# pth.net
KiCad netlist of a schematic drawn in EAGLE
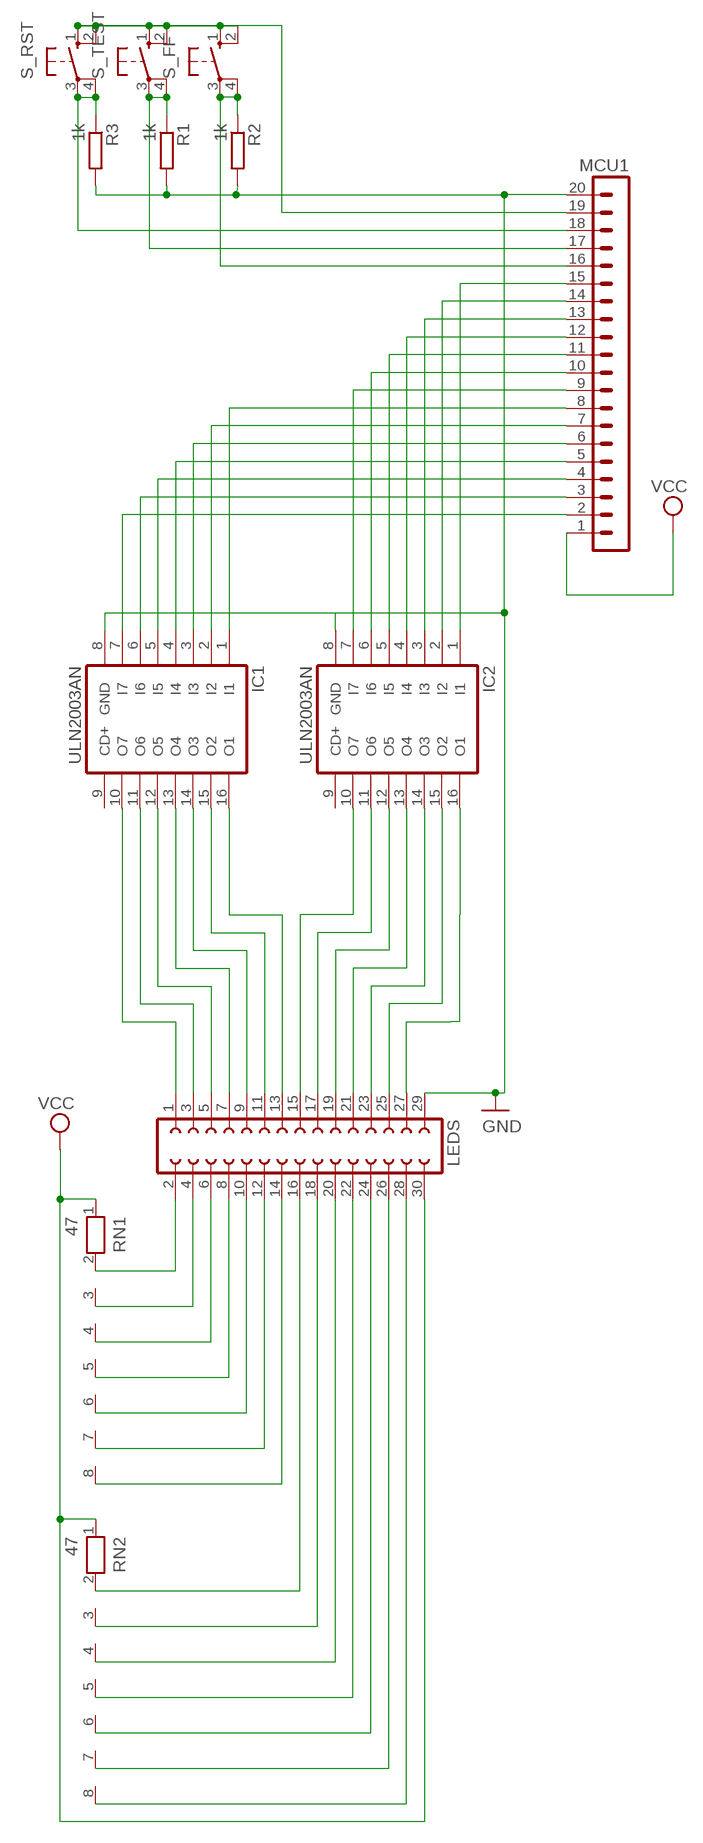
[diagram p0: schematic, sheet 1]

(export (version "E")
  (design (tool "Eeschema 10.0.6"))
  (components
    (comp (ref "IC1")
      (value "ULN2003AN")
      (footprint "eagle-import:DIL16")
      (libsource (lib "eagle-import") (part "ULN2003AN"))
    )
    (comp (ref "IC2")
      (value "ULN2003AN")
      (footprint "eagle-import:DIL16")
      (libsource (lib "eagle-import") (part "ULN2003AN"))
    )
    (comp (ref "LEDS")
      (value "FE15-2")
      (footprint "eagle-import:FE15-2")
      (libsource (lib "eagle-import") (part "FE15-2"))
    )
    (comp (ref "MCU1")
      (value "MA20-1")
      (footprint "eagle-import:MA20-1")
      (libsource (lib "eagle-import") (part "MA20-1"))
    )
    (comp (ref "R1")
      (value "1k")
      (footprint "eagle-import:0207_10")
      (libsource (lib "eagle-import") (part "R-EU_0207/10"))
    )
    (comp (ref "R2")
      (value "1k")
      (footprint "eagle-import:0207_10")
      (libsource (lib "eagle-import") (part "R-EU_0207/10"))
    )
    (comp (ref "R3")
      (value "1k")
      (footprint "eagle-import:0207_10")
      (libsource (lib "eagle-import") (part "R-EU_0207/10"))
    )
    (comp (ref "RN1")
      (value "47")
      (footprint "eagle-import:RN-8")
      (libsource (lib "eagle-import") (part "RN07"))
    )
    (comp (ref "RN2")
      (value "47")
      (footprint "eagle-import:RN-8")
      (libsource (lib "eagle-import") (part "RN07"))
    )
    (comp (ref "S_FF")
      (value "10-XX")
      (footprint "eagle-import:B3F-10XX")
      (fields (field (name "MPN") "B3F-1000"))
      (libsource (lib "eagle-import") (part "10-XX"))
    )
    (comp (ref "S_RST")
      (value "10-XX")
      (footprint "eagle-import:B3F-10XX")
      (fields (field (name "MPN") "B3F-1000"))
      (libsource (lib "eagle-import") (part "10-XX"))
    )
    (comp (ref "S_TEST")
      (value "10-XX")
      (footprint "eagle-import:B3F-10XX")
      (fields (field (name "MPN") "B3F-1000"))
      (libsource (lib "eagle-import") (part "10-XX"))
    )
  )
  (nets
    (net (code "1") (name "GND") (class "Default")
      (node (ref "IC1") (pin "8") (pinfunction "GND_8") (pintype "power_in"))
      (node (ref "IC2") (pin "8") (pinfunction "GND_8") (pintype "power_in"))
      (node (ref "LEDS") (pin "29") (pinfunction "29_29") (pintype "passive"))
      (node (ref "MCU1") (pin "20") (pinfunction "20_20") (pintype "passive"))
      (node (ref "R1") (pin "2") (pinfunction "2_2") (pintype "passive"))
      (node (ref "R2") (pin "2") (pinfunction "2_2") (pintype "passive"))
      (node (ref "R3") (pin "2") (pinfunction "2_2") (pintype "passive"))
    )
    (net (code "2") (name "Net-(IC1-I1)") (class "Default")
      (node (ref "IC1") (pin "1") (pinfunction "I1_1") (pintype "input"))
      (node (ref "MCU1") (pin "8") (pinfunction "8_8") (pintype "passive"))
    )
    (net (code "3") (name "Net-(IC1-I2)") (class "Default")
      (node (ref "IC1") (pin "2") (pinfunction "I2_2") (pintype "input"))
      (node (ref "MCU1") (pin "7") (pinfunction "7_7") (pintype "passive"))
    )
    (net (code "4") (name "Net-(IC1-I3)") (class "Default")
      (node (ref "IC1") (pin "3") (pinfunction "I3_3") (pintype "input"))
      (node (ref "MCU1") (pin "6") (pinfunction "6_6") (pintype "passive"))
    )
    (net (code "5") (name "Net-(IC1-I4)") (class "Default")
      (node (ref "IC1") (pin "4") (pinfunction "I4_4") (pintype "input"))
      (node (ref "MCU1") (pin "5") (pinfunction "5_5") (pintype "passive"))
    )
    (net (code "6") (name "Net-(IC1-I5)") (class "Default")
      (node (ref "IC1") (pin "5") (pinfunction "I5_5") (pintype "input"))
      (node (ref "MCU1") (pin "4") (pinfunction "4_4") (pintype "passive"))
    )
    (net (code "7") (name "Net-(IC1-I6)") (class "Default")
      (node (ref "IC1") (pin "6") (pinfunction "I6_6") (pintype "input"))
      (node (ref "MCU1") (pin "3") (pinfunction "3_3") (pintype "passive"))
    )
    (net (code "8") (name "Net-(IC1-I7)") (class "Default")
      (node (ref "IC1") (pin "7") (pinfunction "I7_7") (pintype "input"))
      (node (ref "MCU1") (pin "2") (pinfunction "2_2") (pintype "passive"))
    )
    (net (code "9") (name "Net-(IC1-O1)") (class "Default")
      (node (ref "IC1") (pin "16") (pinfunction "O1_16") (pintype "open_collector"))
      (node (ref "LEDS") (pin "13") (pinfunction "13_13") (pintype "passive"))
    )
    (net (code "10") (name "Net-(IC1-O2)") (class "Default")
      (node (ref "IC1") (pin "15") (pinfunction "O2_15") (pintype "open_collector"))
      (node (ref "LEDS") (pin "11") (pinfunction "11_11") (pintype "passive"))
    )
    (net (code "11") (name "Net-(IC1-O3)") (class "Default")
      (node (ref "IC1") (pin "14") (pinfunction "O3_14") (pintype "open_collector"))
      (node (ref "LEDS") (pin "9") (pinfunction "9_9") (pintype "passive"))
    )
    (net (code "12") (name "Net-(IC1-O4)") (class "Default")
      (node (ref "IC1") (pin "13") (pinfunction "O4_13") (pintype "open_collector"))
      (node (ref "LEDS") (pin "7") (pinfunction "7_7") (pintype "passive"))
    )
    (net (code "13") (name "Net-(IC1-O5)") (class "Default")
      (node (ref "IC1") (pin "12") (pinfunction "O5_12") (pintype "open_collector"))
      (node (ref "LEDS") (pin "5") (pinfunction "5_5") (pintype "passive"))
    )
    (net (code "14") (name "Net-(IC1-O6)") (class "Default")
      (node (ref "IC1") (pin "11") (pinfunction "O6_11") (pintype "open_collector"))
      (node (ref "LEDS") (pin "3") (pinfunction "3_3") (pintype "passive"))
    )
    (net (code "15") (name "Net-(IC1-O7)") (class "Default")
      (node (ref "IC1") (pin "10") (pinfunction "O7_10") (pintype "open_collector"))
      (node (ref "LEDS") (pin "1") (pinfunction "1_1") (pintype "passive"))
    )
    (net (code "16") (name "Net-(IC2-I1)") (class "Default")
      (node (ref "IC2") (pin "1") (pinfunction "I1_1") (pintype "input"))
      (node (ref "MCU1") (pin "15") (pinfunction "15_15") (pintype "passive"))
    )
    (net (code "17") (name "Net-(IC2-I2)") (class "Default")
      (node (ref "IC2") (pin "2") (pinfunction "I2_2") (pintype "input"))
      (node (ref "MCU1") (pin "14") (pinfunction "14_14") (pintype "passive"))
    )
    (net (code "18") (name "Net-(IC2-I3)") (class "Default")
      (node (ref "IC2") (pin "3") (pinfunction "I3_3") (pintype "input"))
      (node (ref "MCU1") (pin "13") (pinfunction "13_13") (pintype "passive"))
    )
    (net (code "19") (name "Net-(IC2-I4)") (class "Default")
      (node (ref "IC2") (pin "4") (pinfunction "I4_4") (pintype "input"))
      (node (ref "MCU1") (pin "12") (pinfunction "12_12") (pintype "passive"))
    )
    (net (code "20") (name "Net-(IC2-I5)") (class "Default")
      (node (ref "IC2") (pin "5") (pinfunction "I5_5") (pintype "input"))
      (node (ref "MCU1") (pin "11") (pinfunction "11_11") (pintype "passive"))
    )
    (net (code "21") (name "Net-(IC2-I6)") (class "Default")
      (node (ref "IC2") (pin "6") (pinfunction "I6_6") (pintype "input"))
      (node (ref "MCU1") (pin "10") (pinfunction "10_10") (pintype "passive"))
    )
    (net (code "22") (name "Net-(IC2-I7)") (class "Default")
      (node (ref "IC2") (pin "7") (pinfunction "I7_7") (pintype "input"))
      (node (ref "MCU1") (pin "9") (pinfunction "9_9") (pintype "passive"))
    )
    (net (code "23") (name "Net-(IC2-O1)") (class "Default")
      (node (ref "IC2") (pin "16") (pinfunction "O1_16") (pintype "open_collector"))
      (node (ref "LEDS") (pin "27") (pinfunction "27_27") (pintype "passive"))
    )
    (net (code "24") (name "Net-(IC2-O2)") (class "Default")
      (node (ref "IC2") (pin "15") (pinfunction "O2_15") (pintype "open_collector"))
      (node (ref "LEDS") (pin "25") (pinfunction "25_25") (pintype "passive"))
    )
    (net (code "25") (name "Net-(IC2-O3)") (class "Default")
      (node (ref "IC2") (pin "14") (pinfunction "O3_14") (pintype "open_collector"))
      (node (ref "LEDS") (pin "23") (pinfunction "23_23") (pintype "passive"))
    )
    (net (code "26") (name "Net-(IC2-O4)") (class "Default")
      (node (ref "IC2") (pin "13") (pinfunction "O4_13") (pintype "open_collector"))
      (node (ref "LEDS") (pin "21") (pinfunction "21_21") (pintype "passive"))
    )
    (net (code "27") (name "Net-(IC2-O5)") (class "Default")
      (node (ref "IC2") (pin "12") (pinfunction "O5_12") (pintype "open_collector"))
      (node (ref "LEDS") (pin "19") (pinfunction "19_19") (pintype "passive"))
    )
    (net (code "28") (name "Net-(IC2-O6)") (class "Default")
      (node (ref "IC2") (pin "11") (pinfunction "O6_11") (pintype "open_collector"))
      (node (ref "LEDS") (pin "17") (pinfunction "17_17") (pintype "passive"))
    )
    (net (code "29") (name "Net-(IC2-O7)") (class "Default")
      (node (ref "IC2") (pin "10") (pinfunction "O7_10") (pintype "open_collector"))
      (node (ref "LEDS") (pin "15") (pinfunction "15_15") (pintype "passive"))
    )
    (net (code "30") (name "Net-(LEDS-Pad2)") (class "Default")
      (node (ref "LEDS") (pin "2") (pinfunction "2_2") (pintype "passive"))
      (node (ref "RN1") (pin "2") (pinfunction "2_2") (pintype "passive"))
    )
    (net (code "31") (name "Net-(LEDS-Pad4)") (class "Default")
      (node (ref "LEDS") (pin "4") (pinfunction "4_4") (pintype "passive"))
      (node (ref "RN1") (pin "3") (pinfunction "3_3") (pintype "passive"))
    )
    (net (code "32") (name "Net-(LEDS-Pad6)") (class "Default")
      (node (ref "LEDS") (pin "6") (pinfunction "6_6") (pintype "passive"))
      (node (ref "RN1") (pin "4") (pinfunction "4_4") (pintype "passive"))
    )
    (net (code "33") (name "Net-(LEDS-Pad8)") (class "Default")
      (node (ref "LEDS") (pin "8") (pinfunction "8_8") (pintype "passive"))
      (node (ref "RN1") (pin "5") (pinfunction "5_5") (pintype "passive"))
    )
    (net (code "34") (name "Net-(LEDS-Pad10)") (class "Default")
      (node (ref "LEDS") (pin "10") (pinfunction "10_10") (pintype "passive"))
      (node (ref "RN1") (pin "6") (pinfunction "6_6") (pintype "passive"))
    )
    (net (code "35") (name "Net-(LEDS-Pad12)") (class "Default")
      (node (ref "LEDS") (pin "12") (pinfunction "12_12") (pintype "passive"))
      (node (ref "RN1") (pin "7") (pinfunction "7_7") (pintype "passive"))
    )
    (net (code "36") (name "Net-(LEDS-Pad14)") (class "Default")
      (node (ref "LEDS") (pin "14") (pinfunction "14_14") (pintype "passive"))
      (node (ref "RN1") (pin "8") (pinfunction "8_8") (pintype "passive"))
    )
    (net (code "37") (name "Net-(LEDS-Pad16)") (class "Default")
      (node (ref "LEDS") (pin "16") (pinfunction "16_16") (pintype "passive"))
      (node (ref "RN2") (pin "2") (pinfunction "2_2") (pintype "passive"))
    )
    (net (code "38") (name "Net-(LEDS-Pad18)") (class "Default")
      (node (ref "LEDS") (pin "18") (pinfunction "18_18") (pintype "passive"))
      (node (ref "RN2") (pin "3") (pinfunction "3_3") (pintype "passive"))
    )
    (net (code "39") (name "Net-(LEDS-Pad20)") (class "Default")
      (node (ref "LEDS") (pin "20") (pinfunction "20_20") (pintype "passive"))
      (node (ref "RN2") (pin "4") (pinfunction "4_4") (pintype "passive"))
    )
    (net (code "40") (name "Net-(LEDS-Pad22)") (class "Default")
      (node (ref "LEDS") (pin "22") (pinfunction "22_22") (pintype "passive"))
      (node (ref "RN2") (pin "5") (pinfunction "5_5") (pintype "passive"))
    )
    (net (code "41") (name "Net-(LEDS-Pad24)") (class "Default")
      (node (ref "LEDS") (pin "24") (pinfunction "24_24") (pintype "passive"))
      (node (ref "RN2") (pin "6") (pinfunction "6_6") (pintype "passive"))
    )
    (net (code "42") (name "Net-(LEDS-Pad26)") (class "Default")
      (node (ref "LEDS") (pin "26") (pinfunction "26_26") (pintype "passive"))
      (node (ref "RN2") (pin "7") (pinfunction "7_7") (pintype "passive"))
    )
    (net (code "43") (name "Net-(LEDS-Pad28)") (class "Default")
      (node (ref "LEDS") (pin "28") (pinfunction "28_28") (pintype "passive"))
      (node (ref "RN2") (pin "8") (pinfunction "8_8") (pintype "passive"))
    )
    (net (code "44") (name "Net-(S_FF-P)") (class "Default")
      (node (ref "MCU1") (pin "16") (pinfunction "16_16") (pintype "passive"))
      (node (ref "R2") (pin "1") (pinfunction "1_1") (pintype "passive"))
      (node (ref "S_FF") (pin "3") (pinfunction "P_3") (pintype "passive"))
      (node (ref "S_FF") (pin "4") (pinfunction "P1_4") (pintype "passive"))
    )
    (net (code "45") (name "Net-(S_FF-S)") (class "Default")
      (node (ref "MCU1") (pin "19") (pinfunction "19_19") (pintype "passive"))
      (node (ref "S_FF") (pin "1") (pinfunction "S_1") (pintype "passive"))
      (node (ref "S_FF") (pin "2") (pinfunction "S1_2") (pintype "passive"))
      (node (ref "S_RST") (pin "1") (pinfunction "S_1") (pintype "passive"))
      (node (ref "S_RST") (pin "2") (pinfunction "S1_2") (pintype "passive"))
      (node (ref "S_TEST") (pin "1") (pinfunction "S_1") (pintype "passive"))
      (node (ref "S_TEST") (pin "2") (pinfunction "S1_2") (pintype "passive"))
    )
    (net (code "46") (name "Net-(S_RST-P)") (class "Default")
      (node (ref "MCU1") (pin "18") (pinfunction "18_18") (pintype "passive"))
      (node (ref "R3") (pin "1") (pinfunction "1_1") (pintype "passive"))
      (node (ref "S_RST") (pin "3") (pinfunction "P_3") (pintype "passive"))
      (node (ref "S_RST") (pin "4") (pinfunction "P1_4") (pintype "passive"))
    )
    (net (code "47") (name "Net-(S_TEST-P)") (class "Default")
      (node (ref "MCU1") (pin "17") (pinfunction "17_17") (pintype "passive"))
      (node (ref "R1") (pin "1") (pinfunction "1_1") (pintype "passive"))
      (node (ref "S_TEST") (pin "3") (pinfunction "P_3") (pintype "passive"))
      (node (ref "S_TEST") (pin "4") (pinfunction "P1_4") (pintype "passive"))
    )
    (net (code "48") (name "VCC") (class "Default")
      (node (ref "LEDS") (pin "30") (pinfunction "30_30") (pintype "passive"))
      (node (ref "MCU1") (pin "1") (pinfunction "1_1") (pintype "passive"))
      (node (ref "RN1") (pin "1") (pinfunction "1_1") (pintype "passive"))
      (node (ref "RN2") (pin "1") (pinfunction "1_1") (pintype "passive"))
    )
    (net (code "49") (name "unconnected-(IC1-CD+-Pad9)") (class "Default")
      (node (ref "IC1") (pin "9") (pinfunction "CD+_9") (pintype "passive"))
    )
    (net (code "50") (name "unconnected-(IC2-CD+-Pad9)") (class "Default")
      (node (ref "IC2") (pin "9") (pinfunction "CD+_9") (pintype "passive"))
    )
  )
)
